# ESP32_perifericos.net
KiCad netlist of a schematic drawn in Altium Designer
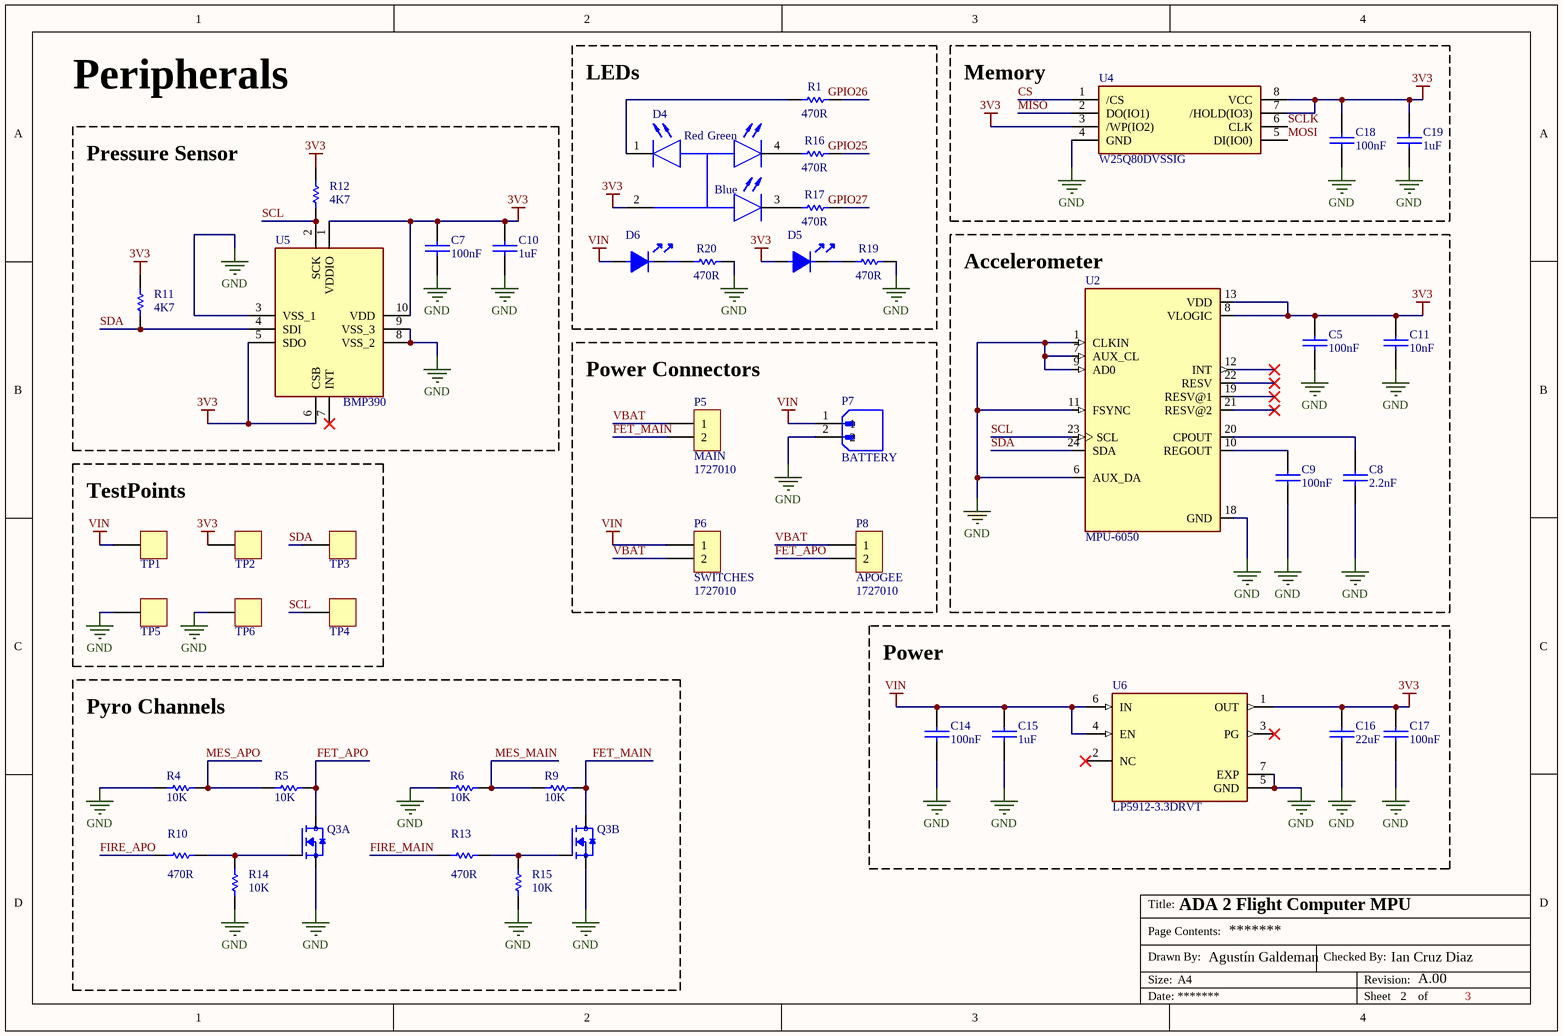
[diagram p0: ESP32 perifericos.SchDoc]

(export (version "E")
  (design (tool "Eeschema 10.0.6"))
  (components
    (comp (ref "C5")
      (value "100nF")
      (footprint "CAPSMD0805")
      (description "Capacitor SMD 4.7nF")
      (fields
        (field (name "MANUFACTURER") "FH (Guangdong Fenghua Advanced Tech)")
        (field (name "MANUFACTURER PART NUMBER") "0805B104M500NT")
      )
      (libsource (lib "ESP32 Platform") (part "CAP"))
    )
    (comp (ref "C7")
      (value "100nF")
      (footprint "CAPSMD0805")
      (description "Capacitor SMD 4.7nF")
      (fields
        (field (name "MANUFACTURER") "FH (Guangdong Fenghua Advanced Tech)")
        (field (name "MANUFACTURER PART NUMBER") "0805B104M500NT")
      )
      (libsource (lib "ESP32 Platform") (part "CAP"))
    )
    (comp (ref "C8")
      (value "2.2nF")
      (footprint "CAPSMD0805")
      (description "Capacitor SMD 4.7nF")
      (fields
        (field (name "MANUFACTURER") "YAGEO")
        (field (name "MANUFACTURER PART NUMBER") "CC0805JRX7R0BB222")
      )
      (libsource (lib "ESP32 Platform") (part "CAP"))
    )
    (comp (ref "C9")
      (value "100nF")
      (footprint "CAPSMD0805")
      (description "Capacitor SMD 4.7nF")
      (fields
        (field (name "MANUFACTURER") "FH (Guangdong Fenghua Advanced Tech)")
        (field (name "MANUFACTURER PART NUMBER") "0805B104M500NT")
      )
      (libsource (lib "ESP32 Platform") (part "CAP"))
    )
    (comp (ref "C10")
      (value "1uF")
      (footprint "CAPSMD0805")
      (description "Capacitor SMD 4.7nF")
      (fields
        (field (name "MANUFACTURER") "FH (Guangdong Fenghua Advanced Tech)")
        (field (name "MANUFACTURER PART NUMBER") "0805F105Z250NT")
      )
      (libsource (lib "ESP32 Platform") (part "CAP"))
    )
    (comp (ref "C11")
      (value "10nF")
      (footprint "CAPSMD0805")
      (description "Capacitor SMD 4.7nF")
      (fields
        (field (name "MANUFACTURER") "PSA(Prosperity Dielectrics)")
        (field (name "MANUFACTURER PART NUMBER") "FN21X103K500PXG")
      )
      (libsource (lib "ESP32 Platform") (part "CAP"))
    )
    (comp (ref "C14")
      (value "100nF")
      (footprint "CAPSMD0805")
      (description "Capacitor SMD 4.7nF")
      (fields
        (field (name "MANUFACTURER") "FH (Guangdong Fenghua Advanced Tech)")
        (field (name "MANUFACTURER PART NUMBER") "0805B104M500NT")
      )
      (libsource (lib "ESP32 Platform") (part "CAP"))
    )
    (comp (ref "C15")
      (value "1uF")
      (footprint "CAPSMD0805")
      (description "Capacitor SMD 4.7nF")
      (fields
        (field (name "MANUFACTURER") "FH (Guangdong Fenghua Advanced Tech)")
        (field (name "MANUFACTURER PART NUMBER") "0805F105Z250NT")
      )
      (libsource (lib "ESP32 Platform") (part "CAP"))
    )
    (comp (ref "C16")
      (value "22uF")
      (footprint "CAPSMD0805")
      (description "Capacitor SMD 4.7nF")
      (fields
        (field (name "MANUFACTURER") "Samsung Electro-Mechanics")
        (field (name "MANUFACTURER PART NUMBER") "CL21A226KPCLRNC")
      )
      (libsource (lib "ESP32 Platform") (part "CAP"))
    )
    (comp (ref "C17")
      (value "100nF")
      (footprint "CAPSMD0805")
      (description "Capacitor SMD 4.7nF")
      (fields
        (field (name "MANUFACTURER") "FH (Guangdong Fenghua Advanced Tech)")
        (field (name "MANUFACTURER PART NUMBER") "0805B104M500NT")
      )
      (libsource (lib "ESP32 Platform") (part "CAP"))
    )
    (comp (ref "C18")
      (value "100nF")
      (footprint "CAPSMD0805")
      (description "Capacitor SMD 4.7nF")
      (fields
        (field (name "MANUFACTURER") "FH (Guangdong Fenghua Advanced Tech)")
        (field (name "MANUFACTURER PART NUMBER") "0805B104M500NT")
      )
      (libsource (lib "ESP32 Platform") (part "CAP"))
    )
    (comp (ref "C19")
      (value "1uF")
      (footprint "CAPSMD0805")
      (description "Capacitor SMD 4.7nF")
      (fields
        (field (name "MANUFACTURER") "FH (Guangdong Fenghua Advanced Tech)")
        (field (name "MANUFACTURER PART NUMBER") "0805F105Z250NT")
      )
      (libsource (lib "ESP32 Platform") (part "CAP"))
    )
    (comp (ref "D4")
      (value "~")
      (footprint "4-PLCC")
      (fields
        (field (name "MANUFACTURER") "CREELED, INC.")
        (field (name "MANUFACTURER PART NUMBER") "CLVBA-FKA-CAEDH8BBB7A363")
      )
      (libsource (lib "ESP32 Platform") (part "LED RGB"))
    )
    (comp (ref "D5")
      (value "~")
      (footprint "LEDSMD0603")
      (description "LED SMD Verde")
      (fields
        (field (name "MANUFACTURER") "Everlight Elec")
        (field (name "MANUFACTURER PART NUMBER") "19-217/R6C-AL1M2VY/3T")
      )
      (libsource (lib "ESP32 Platform") (part "LED"))
    )
    (comp (ref "D6")
      (value "~")
      (footprint "LEDSMD0603")
      (description "LED SMD Verde")
      (fields
        (field (name "MANUFACTURER") "Everlight Elec")
        (field (name "MANUFACTURER PART NUMBER") "19-217/R6C-AL1M2VY/3T")
      )
      (libsource (lib "ESP32 Platform") (part "LED"))
    )
    (comp (ref "P5")
      (value "MAIN")
      (footprint "BORNERA2")
      (description "13.5A 200V Green Straight pin 3.81mm 1 2 Plugin,P=3.81mm  Screw terminal ROHS")
      (fields
        (field (name "MANUFACTURER") "Phoenix Contact")
        (field (name "MANUFACTURER PART NUMBER") "1727010")
      )
      (libsource (lib "ESP32 Platform") (part "BORNERA 2"))
    )
    (comp (ref "P6")
      (value "SWITCHES")
      (footprint "BORNERA2")
      (description "13.5A 200V Green Straight pin 3.81mm 1 2 Plugin,P=3.81mm  Screw terminal ROHS")
      (fields
        (field (name "MANUFACTURER") "Phoenix Contact")
        (field (name "MANUFACTURER PART NUMBER") "1727010")
      )
      (libsource (lib "ESP32 Platform") (part "BORNERA 2"))
    )
    (comp (ref "P7")
      (value "BATTERY")
      (footprint "JST_BM02B-GHS-TBT(LF)(SN)")
      (description "Connector Header Surface Mount 2 position 0.049 (1.25mm)")
      (fields
        (field (name "MANUFACTURER") "JST Sales America")
        (field (name "MANUFACTURER PART NUMBER") "BM02B-GHS-TBT(LF)(SN)")
      )
      (libsource (lib "ESP32 Platform") (part "BM02B-GHS-TBT(LF)(SN)"))
    )
    (comp (ref "P8")
      (value "APOGEE")
      (footprint "BORNERA2")
      (description "13.5A 200V Green Straight pin 3.81mm 1 2 Plugin,P=3.81mm  Screw terminal ROHS")
      (fields
        (field (name "MANUFACTURER") "Phoenix Contact")
        (field (name "MANUFACTURER PART NUMBER") "1727010")
      )
      (libsource (lib "ESP32 Platform") (part "BORNERA 2"))
    )
    (comp (ref "Q3")
      (value "~")
      (footprint "TRANS_TSM200N03DPQ33_RGG")
      (description "MOSFET 2 N-CH 30V 20A 8PDFN")
      (fields
        (field (name "MANUFACTURER") "Taiwan Semiconductor Corporation")
        (field (name "MANUFACTURER PART NUMBER") "TSM200N03DPQ33 RGG")
      )
      (libsource (lib "ESP32 Platform") (part "TSM200N03DPQ33_RGG"))
    )
    (comp (ref "R1")
      (value "470R")
      (footprint "0805")
      (description "Resistencia SMD 470ohms")
      (fields
        (field (name "MANUFACTURER") "UNI-ROYAL(Uniroyal Elec)")
        (field (name "MANUFACTURER PART NUMBER") "CQ05W8J0471T5E")
      )
      (libsource (lib "ESP32 Platform") (part "RES"))
    )
    (comp (ref "R4")
      (value "10K")
      (footprint "0805")
      (description "Resistencia SMD 470ohms")
      (fields
        (field (name "MANUFACTURER") "Viking Tech")
        (field (name "MANUFACTURER PART NUMBER") "ARG05BTC1002")
      )
      (libsource (lib "ESP32 Platform") (part "RES"))
    )
    (comp (ref "R5")
      (value "10K")
      (footprint "0805")
      (description "Resistencia SMD 470ohms")
      (fields
        (field (name "MANUFACTURER") "Viking Tech")
        (field (name "MANUFACTURER PART NUMBER") "ARG05BTC1002")
      )
      (libsource (lib "ESP32 Platform") (part "RES"))
    )
    (comp (ref "R6")
      (value "10K")
      (footprint "0805")
      (description "Resistencia SMD 470ohms")
      (fields
        (field (name "MANUFACTURER") "Viking Tech")
        (field (name "MANUFACTURER PART NUMBER") "ARG05BTC1002")
      )
      (libsource (lib "ESP32 Platform") (part "RES"))
    )
    (comp (ref "R9")
      (value "10K")
      (footprint "0805")
      (description "Resistencia SMD 470ohms")
      (fields
        (field (name "MANUFACTURER") "Viking Tech")
        (field (name "MANUFACTURER PART NUMBER") "ARG05BTC1002")
      )
      (libsource (lib "ESP32 Platform") (part "RES"))
    )
    (comp (ref "R10")
      (value "470R")
      (footprint "0805")
      (description "Resistencia SMD 470ohms")
      (fields
        (field (name "MANUFACTURER") "UNI-ROYAL(Uniroyal Elec)")
        (field (name "MANUFACTURER PART NUMBER") "CQ05W8J0471T5E")
      )
      (libsource (lib "ESP32 Platform") (part "RES"))
    )
    (comp (ref "R11")
      (value "4K7")
      (footprint "0805")
      (description "Resistencia SMD 470ohms")
      (fields
        (field (name "MANUFACTURER") "Viking Tech")
        (field (name "MANUFACTURER PART NUMBER") "CR-05FL7---4K7")
      )
      (libsource (lib "ESP32 Platform") (part "RES"))
    )
    (comp (ref "R12")
      (value "4K7")
      (footprint "0805")
      (description "Resistencia SMD 470ohms")
      (fields
        (field (name "MANUFACTURER") "Viking Tech")
        (field (name "MANUFACTURER PART NUMBER") "CR-05FL7---4K7")
      )
      (libsource (lib "ESP32 Platform") (part "RES"))
    )
    (comp (ref "R13")
      (value "470R")
      (footprint "0805")
      (description "Resistencia SMD 470ohms")
      (fields
        (field (name "MANUFACTURER") "UNI-ROYAL(Uniroyal Elec)")
        (field (name "MANUFACTURER PART NUMBER") "CQ05W8J0471T5E")
      )
      (libsource (lib "ESP32 Platform") (part "RES"))
    )
    (comp (ref "R14")
      (value "10K")
      (footprint "0805")
      (description "Resistencia SMD 470ohms")
      (fields
        (field (name "MANUFACTURER") "Viking Tech")
        (field (name "MANUFACTURER PART NUMBER") "ARG05BTC1002")
      )
      (libsource (lib "ESP32 Platform") (part "RES"))
    )
    (comp (ref "R15")
      (value "10K")
      (footprint "0805")
      (description "Resistencia SMD 470ohms")
      (fields
        (field (name "MANUFACTURER") "Viking Tech")
        (field (name "MANUFACTURER PART NUMBER") "ARG05BTC1002")
      )
      (libsource (lib "ESP32 Platform") (part "RES"))
    )
    (comp (ref "R16")
      (value "470R")
      (footprint "0805")
      (description "Resistencia SMD 470ohms")
      (fields
        (field (name "MANUFACTURER") "UNI-ROYAL(Uniroyal Elec)")
        (field (name "MANUFACTURER PART NUMBER") "CQ05W8J0471T5E")
      )
      (libsource (lib "ESP32 Platform") (part "RES"))
    )
    (comp (ref "R17")
      (value "470R")
      (footprint "0805")
      (description "Resistencia SMD 470ohms")
      (fields
        (field (name "MANUFACTURER") "UNI-ROYAL(Uniroyal Elec)")
        (field (name "MANUFACTURER PART NUMBER") "CQ05W8J0471T5E")
      )
      (libsource (lib "ESP32 Platform") (part "RES"))
    )
    (comp (ref "R19")
      (value "470R")
      (footprint "0805")
      (description "Resistencia SMD 470ohms")
      (fields
        (field (name "MANUFACTURER") "UNI-ROYAL(Uniroyal Elec)")
        (field (name "MANUFACTURER PART NUMBER") "CQ05W8J0471T5E")
      )
      (libsource (lib "ESP32 Platform") (part "RES"))
    )
    (comp (ref "R20")
      (value "470R")
      (footprint "0805")
      (description "Resistencia SMD 470ohms")
      (fields
        (field (name "MANUFACTURER") "UNI-ROYAL(Uniroyal Elec)")
        (field (name "MANUFACTURER PART NUMBER") "CQ05W8J0471T5E")
      )
      (libsource (lib "ESP32 Platform") (part "RES"))
    )
    (comp (ref "TP1")
      (value "VIN")
      (footprint "5015")
      (description "Thimble/Copper Rod/Test Ring ROHS")
      (fields (field (name "MANUFACTURER") "Ronghe") (field (name "MANUFACTURER PART NUMBER") "RH-5015"))
      (libsource (lib "ESP32 Platform") (part "TESTPOINT_5015"))
    )
    (comp (ref "TP2")
      (value "3V3")
      (footprint "5015")
      (description "Thimble/Copper Rod/Test Ring ROHS")
      (fields (field (name "MANUFACTURER") "Ronghe") (field (name "MANUFACTURER PART NUMBER") "RH-5015"))
      (libsource (lib "ESP32 Platform") (part "TESTPOINT_5015"))
    )
    (comp (ref "TP3")
      (value "SDA")
      (footprint "5015")
      (description "Thimble/Copper Rod/Test Ring ROHS")
      (fields (field (name "MANUFACTURER") "Ronghe") (field (name "MANUFACTURER PART NUMBER") "RH-5015"))
      (libsource (lib "ESP32 Platform") (part "TESTPOINT_5015"))
    )
    (comp (ref "TP4")
      (value "SCL")
      (footprint "5015")
      (description "Thimble/Copper Rod/Test Ring ROHS")
      (fields (field (name "MANUFACTURER") "Ronghe") (field (name "MANUFACTURER PART NUMBER") "RH-5015"))
      (libsource (lib "ESP32 Platform") (part "TESTPOINT_5015"))
    )
    (comp (ref "TP5")
      (value "GND")
      (footprint "5015")
      (description "Thimble/Copper Rod/Test Ring ROHS")
      (fields (field (name "MANUFACTURER") "Ronghe") (field (name "MANUFACTURER PART NUMBER") "RH-5015"))
      (libsource (lib "ESP32 Platform") (part "TESTPOINT_5015"))
    )
    (comp (ref "TP6")
      (value "GND")
      (footprint "5015")
      (description "Thimble/Copper Rod/Test Ring ROHS")
      (fields (field (name "MANUFACTURER") "Ronghe") (field (name "MANUFACTURER PART NUMBER") "RH-5015"))
      (libsource (lib "ESP32 Platform") (part "TESTPOINT_5015"))
    )
    (comp (ref "U2")
      (value "~")
      (footprint "QFN24")
      (description "MPU-6050 series Accelerometer, Gyroscope, 3 Axis Sensor Evaluation Board")
      (fields
        (field (name "MANUFACTURER") "TDK InvenSense")
        (field (name "MANUFACTURER PART NUMBER") "MPU-6050")
      )
      (libsource (lib "ESP32 Platform") (part "MPU-6050"))
    )
    (comp (ref "U4")
      (value "~")
      (footprint "SOIC127P790X216-8N")
      (description "8M-bit 3.0V Serial Flash Memory with uniform 4KB sectors and Dual/Quad SPI")
      (fields
        (field (name "MANUFACTURER") "Winbond Elec")
        (field (name "MANUFACTURER PART NUMBER") "W25Q80DVSSIG")
      )
      (libsource (lib "ESP32 Platform") (part "W25Q80DVSSIG"))
    )
    (comp (ref "U5")
      (value "~")
      (footprint "BMP390")
      (description "Board Mount Pressure Sensors")
      (fields (field (name "MANUFACTURER") "BOSCH") (field (name "MANUFACTURER PART NUMBER") "BMP390"))
      (libsource (lib "ESP32 Platform") (part "BMP390"))
    )
    (comp (ref "U6")
      (value "~")
      (footprint "SON65P200X200X80-7N")
      (fields
        (field (name "MANUFACTURER") "Texas Instruments")
        (field (name "MANUFACTURER PART NUMBER") "LP5912-3.3DRVT")
      )
      (libsource (lib "ESP32 Platform") (part "LP5912-3.3DRVT"))
    )
  )
  (nets
    (net (code "1") (name "/CS") (class "Default")
      (node (ref "U4") (pin "1") (pinfunction "/CS_1") (pintype "passive"))
    )
    (net (code "2") (name "/FET_APO") (class "Default")
      (node (ref "P8") (pin "2") (pinfunction "2_2") (pintype "passive"))
      (node (ref "Q3") (pin "7_8") (pinfunction "D1_7_8") (pintype "passive"))
      (node (ref "R5") (pin "2") (pinfunction "2_2") (pintype "passive"))
    )
    (net (code "3") (name "/FET_MAIN") (class "Default")
      (node (ref "P5") (pin "2") (pinfunction "2_2") (pintype "passive"))
      (node (ref "Q3") (pin "5_6") (pinfunction "D2_5_6") (pintype "passive"))
      (node (ref "R9") (pin "2") (pinfunction "2_2") (pintype "passive"))
    )
    (net (code "4") (name "/FIRE_APO") (class "Default")
      (node (ref "R10") (pin "1") (pinfunction "1_1") (pintype "passive"))
    )
    (net (code "5") (name "/FIRE_MAIN") (class "Default")
      (node (ref "R13") (pin "1") (pinfunction "1_1") (pintype "passive"))
    )
    (net (code "6") (name "/GPIO25") (class "Default")
      (node (ref "R16") (pin "2") (pinfunction "2_2") (pintype "passive"))
    )
    (net (code "7") (name "/GPIO26") (class "Default")
      (node (ref "R1") (pin "2") (pinfunction "2_2") (pintype "passive"))
    )
    (net (code "8") (name "/GPIO27") (class "Default")
      (node (ref "R17") (pin "2") (pinfunction "2_2") (pintype "passive"))
    )
    (net (code "9") (name "/MES_APO") (class "Default")
      (node (ref "R4") (pin "2") (pinfunction "2_2") (pintype "passive"))
      (node (ref "R5") (pin "1") (pinfunction "1_1") (pintype "passive"))
    )
    (net (code "10") (name "/MES_MAIN") (class "Default")
      (node (ref "R6") (pin "2") (pinfunction "2_2") (pintype "passive"))
      (node (ref "R9") (pin "1") (pinfunction "1_1") (pintype "passive"))
    )
    (net (code "11") (name "/MISO") (class "Default")
      (node (ref "U4") (pin "2") (pinfunction "DO(IO1)_2") (pintype "passive"))
    )
    (net (code "12") (name "/MOSI") (class "Default")
      (node (ref "U4") (pin "5") (pinfunction "DI(IO0)_5") (pintype "passive"))
    )
    (net (code "13") (name "/SCL") (class "Default")
      (node (ref "R12") (pin "1") (pinfunction "1_1") (pintype "passive"))
      (node (ref "TP4") (pin "1") (pinfunction "1_1") (pintype "passive"))
      (node (ref "U2") (pin "23") (pinfunction "SCL_23") (pintype "input"))
      (node (ref "U5") (pin "2") (pinfunction "SCK_2") (pintype "passive"))
    )
    (net (code "14") (name "/SCLK") (class "Default")
      (node (ref "U4") (pin "6") (pinfunction "CLK_6") (pintype "passive"))
    )
    (net (code "15") (name "/SDA") (class "Default")
      (node (ref "R11") (pin "1") (pinfunction "1_1") (pintype "passive"))
      (node (ref "TP3") (pin "1") (pinfunction "1_1") (pintype "passive"))
      (node (ref "U2") (pin "24") (pinfunction "SDA_24") (pintype "bidirectional"))
      (node (ref "U5") (pin "4") (pinfunction "SDI_4") (pintype "passive"))
    )
    (net (code "16") (name "/VBAT") (class "Default")
      (node (ref "P5") (pin "1") (pinfunction "1_1") (pintype "passive"))
      (node (ref "P6") (pin "2") (pinfunction "2_2") (pintype "passive"))
      (node (ref "P8") (pin "1") (pinfunction "1_1") (pintype "passive"))
    )
    (net (code "17") (name "3V3") (class "Default")
      (node (ref "C10") (pin "1") (pinfunction "1_1") (pintype "passive"))
      (node (ref "C11") (pin "1") (pinfunction "1_1") (pintype "passive"))
      (node (ref "C16") (pin "1") (pinfunction "1_1") (pintype "passive"))
      (node (ref "C17") (pin "2") (pinfunction "2_2") (pintype "passive"))
      (node (ref "C18") (pin "2") (pinfunction "2_2") (pintype "passive"))
      (node (ref "C19") (pin "1") (pinfunction "1_1") (pintype "passive"))
      (node (ref "C5") (pin "2") (pinfunction "2_2") (pintype "passive"))
      (node (ref "C7") (pin "2") (pinfunction "2_2") (pintype "passive"))
      (node (ref "D4") (pin "2") (pinfunction "A_2") (pintype "passive"))
      (node (ref "D5") (pin "A") (pinfunction "A_A") (pintype "passive"))
      (node (ref "R11") (pin "2") (pinfunction "2_2") (pintype "passive"))
      (node (ref "R12") (pin "2") (pinfunction "2_2") (pintype "passive"))
      (node (ref "TP2") (pin "1") (pinfunction "1_1") (pintype "passive"))
      (node (ref "U2") (pin "13") (pinfunction "VDD_13") (pintype "power_in"))
      (node (ref "U2") (pin "8") (pinfunction "VLOGIC_8") (pintype "power_in"))
      (node (ref "U4") (pin "3") (pinfunction "/WP(IO2)_3") (pintype "passive"))
      (node (ref "U4") (pin "7") (pinfunction "/HOLD(IO3)_7") (pintype "passive"))
      (node (ref "U4") (pin "8") (pinfunction "VCC_8") (pintype "passive"))
      (node (ref "U5") (pin "1") (pinfunction "VDDIO_1") (pintype "passive"))
      (node (ref "U5") (pin "10") (pinfunction "VDD_10") (pintype "passive"))
      (node (ref "U5") (pin "5") (pinfunction "SDO_5") (pintype "passive"))
      (node (ref "U5") (pin "6") (pinfunction "CSB_6") (pintype "passive"))
      (node (ref "U6") (pin "1") (pinfunction "OUT_1") (pintype "output"))
    )
    (net (code "18") (name "GND") (class "Default")
      (node (ref "C10") (pin "2") (pinfunction "2_2") (pintype "passive"))
      (node (ref "C11") (pin "2") (pinfunction "2_2") (pintype "passive"))
      (node (ref "C14") (pin "1") (pinfunction "1_1") (pintype "passive"))
      (node (ref "C15") (pin "2") (pinfunction "2_2") (pintype "passive"))
      (node (ref "C16") (pin "2") (pinfunction "2_2") (pintype "passive"))
      (node (ref "C17") (pin "1") (pinfunction "1_1") (pintype "passive"))
      (node (ref "C18") (pin "1") (pinfunction "1_1") (pintype "passive"))
      (node (ref "C19") (pin "2") (pinfunction "2_2") (pintype "passive"))
      (node (ref "C5") (pin "1") (pinfunction "1_1") (pintype "passive"))
      (node (ref "C7") (pin "1") (pinfunction "1_1") (pintype "passive"))
      (node (ref "C8") (pin "2") (pinfunction "2_2") (pintype "passive"))
      (node (ref "C9") (pin "1") (pinfunction "1_1") (pintype "passive"))
      (node (ref "P7") (pin "2") (pinfunction "2_2") (pintype "passive"))
      (node (ref "Q3") (pin "1") (pinfunction "S1_1") (pintype "passive"))
      (node (ref "Q3") (pin "3") (pinfunction "S2_3") (pintype "passive"))
      (node (ref "R14") (pin "2") (pinfunction "2_2") (pintype "passive"))
      (node (ref "R15") (pin "2") (pinfunction "2_2") (pintype "passive"))
      (node (ref "R19") (pin "2") (pinfunction "2_2") (pintype "passive"))
      (node (ref "R20") (pin "2") (pinfunction "2_2") (pintype "passive"))
      (node (ref "R4") (pin "1") (pinfunction "1_1") (pintype "passive"))
      (node (ref "R6") (pin "1") (pinfunction "1_1") (pintype "passive"))
      (node (ref "TP5") (pin "1") (pinfunction "1_1") (pintype "passive"))
      (node (ref "TP6") (pin "1") (pinfunction "1_1") (pintype "passive"))
      (node (ref "U2") (pin "1") (pinfunction "CLKIN_1") (pintype "input"))
      (node (ref "U2") (pin "11") (pinfunction "FSYNC_11") (pintype "input"))
      (node (ref "U2") (pin "18") (pinfunction "GND_18") (pintype "power_in"))
      (node (ref "U2") (pin "6") (pinfunction "AUX_DA_6") (pintype "bidirectional"))
      (node (ref "U2") (pin "7") (pinfunction "AUX_CL_7") (pintype "input"))
      (node (ref "U2") (pin "9") (pinfunction "AD0_9") (pintype "input"))
      (node (ref "U4") (pin "4") (pinfunction "GND_4") (pintype "passive"))
      (node (ref "U5") (pin "3") (pinfunction "VSS_1_3") (pintype "passive"))
      (node (ref "U5") (pin "8") (pinfunction "VSS_2_8") (pintype "passive"))
      (node (ref "U5") (pin "9") (pinfunction "VSS_3_9") (pintype "passive"))
      (node (ref "U6") (pin "5") (pinfunction "GND_5") (pintype "power_in"))
      (node (ref "U6") (pin "7") (pinfunction "EXP_7") (pintype "power_in"))
    )
    (net (code "19") (name "Net-(D4-BLUE_C)") (class "Default")
      (node (ref "D4") (pin "3") (pinfunction "BLUE_C_3") (pintype "passive"))
      (node (ref "R17") (pin "1") (pinfunction "1_1") (pintype "passive"))
    )
    (net (code "20") (name "Net-(D4-GREEN_C)") (class "Default")
      (node (ref "D4") (pin "4") (pinfunction "GREEN_C_4") (pintype "passive"))
      (node (ref "R16") (pin "1") (pinfunction "1_1") (pintype "passive"))
    )
    (net (code "21") (name "Net-(D4-RED_C)") (class "Default")
      (node (ref "D4") (pin "1") (pinfunction "RED_C_1") (pintype "passive"))
      (node (ref "R1") (pin "1") (pinfunction "1_1") (pintype "passive"))
    )
    (net (code "22") (name "Net-(D5-PadK)") (class "Default")
      (node (ref "D5") (pin "K") (pinfunction "K_K") (pintype "passive"))
      (node (ref "R19") (pin "1") (pinfunction "1_1") (pintype "passive"))
    )
    (net (code "23") (name "Net-(D6-PadK)") (class "Default")
      (node (ref "D6") (pin "K") (pinfunction "K_K") (pintype "passive"))
      (node (ref "R20") (pin "1") (pinfunction "1_1") (pintype "passive"))
    )
    (net (code "24") (name "Net-(Q3A-G1)") (class "Default")
      (node (ref "Q3") (pin "2") (pinfunction "G1_2") (pintype "passive"))
      (node (ref "R10") (pin "2") (pinfunction "2_2") (pintype "passive"))
      (node (ref "R14") (pin "1") (pinfunction "1_1") (pintype "passive"))
    )
    (net (code "25") (name "Net-(Q3B-G2)") (class "Default")
      (node (ref "Q3") (pin "4") (pinfunction "G2_4") (pintype "passive"))
      (node (ref "R13") (pin "2") (pinfunction "2_2") (pintype "passive"))
      (node (ref "R15") (pin "1") (pinfunction "1_1") (pintype "passive"))
    )
    (net (code "26") (name "Net-(U2-CPOUT)") (class "Default")
      (node (ref "C8") (pin "1") (pinfunction "1_1") (pintype "passive"))
      (node (ref "U2") (pin "20") (pinfunction "CPOUT_20") (pintype "passive"))
    )
    (net (code "27") (name "Net-(U2-REGOUT)") (class "Default")
      (node (ref "C9") (pin "2") (pinfunction "2_2") (pintype "passive"))
      (node (ref "U2") (pin "10") (pinfunction "REGOUT_10") (pintype "passive"))
    )
    (net (code "28") (name "VIN") (class "Default")
      (node (ref "C14") (pin "2") (pinfunction "2_2") (pintype "passive"))
      (node (ref "C15") (pin "1") (pinfunction "1_1") (pintype "passive"))
      (node (ref "D6") (pin "A") (pinfunction "A_A") (pintype "passive"))
      (node (ref "P6") (pin "1") (pinfunction "1_1") (pintype "passive"))
      (node (ref "P7") (pin "1") (pinfunction "1_1") (pintype "passive"))
      (node (ref "TP1") (pin "1") (pinfunction "1_1") (pintype "passive"))
      (node (ref "U6") (pin "4") (pinfunction "EN_4") (pintype "input"))
      (node (ref "U6") (pin "6") (pinfunction "IN_6") (pintype "input"))
    )
    (net (code "29") (name "unconnected-(U2-INT-Pad12)") (class "Default")
      (node (ref "U2") (pin "12") (pinfunction "INT_12") (pintype "output+no_connect"))
    )
    (net (code "30") (name "unconnected-(U2-RESV-Pad22)") (class "Default")
      (node (ref "U2") (pin "22") (pinfunction "RESV_22") (pintype "passive+no_connect"))
    )
    (net (code "31") (name "unconnected-(U2-RESV@1-Pad19)") (class "Default")
      (node (ref "U2") (pin "19") (pinfunction "RESV@1_19") (pintype "passive+no_connect"))
    )
    (net (code "32") (name "unconnected-(U2-RESV@2-Pad21)") (class "Default")
      (node (ref "U2") (pin "21") (pinfunction "RESV@2_21") (pintype "passive+no_connect"))
    )
    (net (code "33") (name "unconnected-(U5-INT-Pad7)") (class "Default")
      (node (ref "U5") (pin "7") (pinfunction "INT_7") (pintype "passive+no_connect"))
    )
    (net (code "34") (name "unconnected-(U6-NC-Pad2)") (class "Default")
      (node (ref "U6") (pin "2") (pinfunction "NC_2") (pintype "passive+no_connect"))
    )
    (net (code "35") (name "unconnected-(U6-PG-Pad3)") (class "Default")
      (node (ref "U6") (pin "3") (pinfunction "PG_3") (pintype "output+no_connect"))
    )
  )
)
